# panelolu_2_1.net
KiCad netlist of a schematic drawn in EAGLE
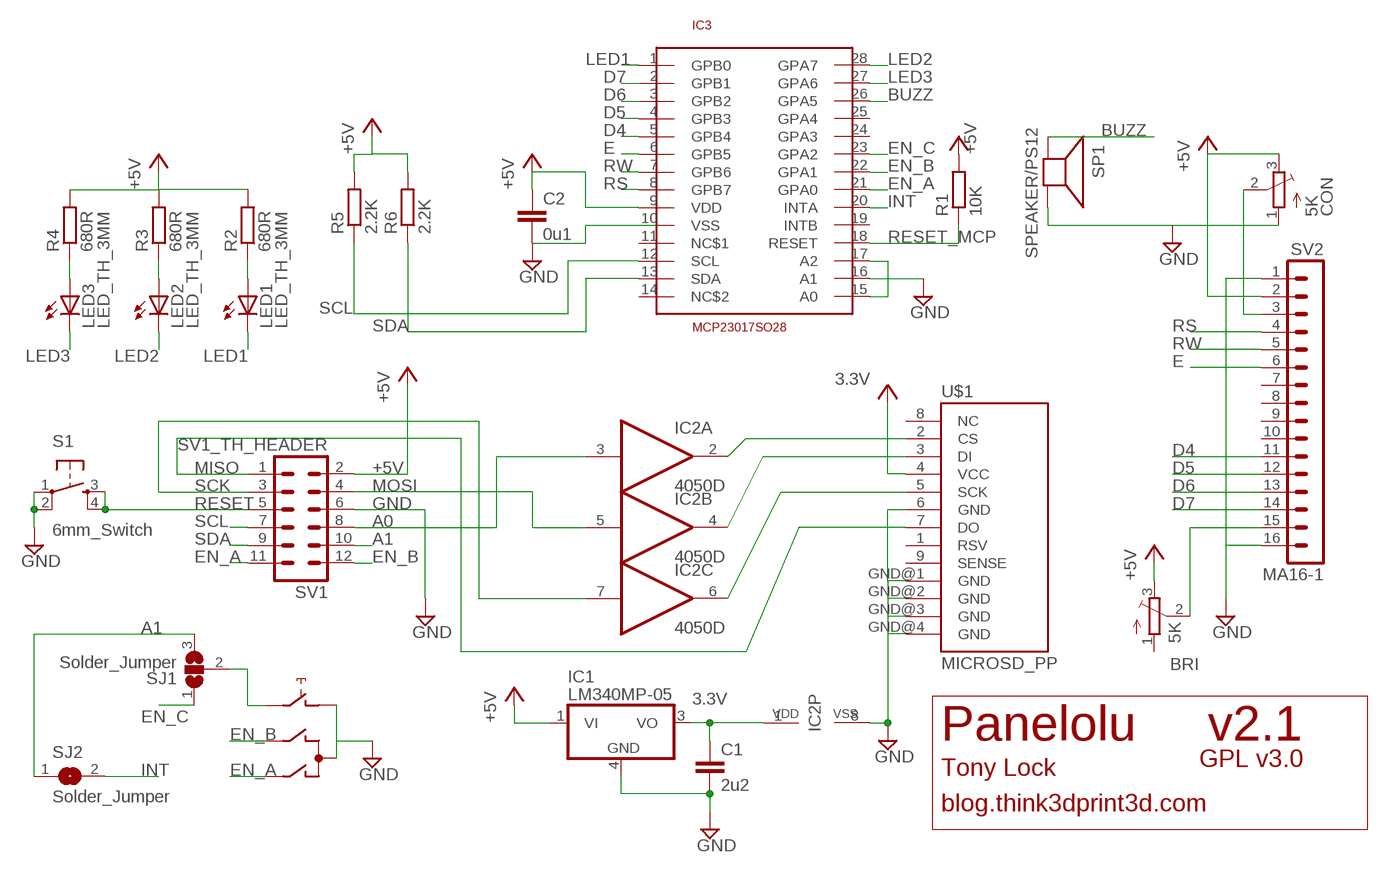
[diagram p0: schematic, sheet 1]

(export (version "E")
  (design (tool "Eeschema 10.0.6"))
  (components
    (comp (ref "BRI")
      (value "5K")
      (footprint "eagle-import:TC33X")
      (libsource (lib "eagle-import") (part "TRIMPOTTC33X"))
    )
    (comp (ref "C1")
      (value "2u2")
      (footprint "eagle-import:C1206K")
      (libsource (lib "eagle-import") (part "C-EUC1206K"))
    )
    (comp (ref "C2")
      (value "0u1")
      (footprint "eagle-import:C0805K")
      (libsource (lib "eagle-import") (part "resistor_C-EUC0805K"))
    )
    (comp (ref "CON")
      (value "5K")
      (footprint "eagle-import:TC33X")
      (libsource (lib "eagle-import") (part "TRIMPOTTC33X"))
    )
    (comp (ref "IC1")
      (value "LM340MP-05")
      (footprint "eagle-import:SOT223")
      (libsource (lib "eagle-import") (part "LM340?-MP05"))
    )
    (comp (ref "IC2")
      (value "4050D")
      (footprint "eagle-import:SO16")
      (libsource (lib "eagle-import") (part "4050D"))
    )
    (comp (ref "IC3")
      (value "MCP23017SO28")
      (footprint "eagle-import:SO28W")
      (libsource (lib "eagle-import") (part "MCP23017SO28"))
    )
    (comp (ref "LED1")
      (value "LED_TH_3MM")
      (footprint "eagle-import:LED3MM")
      (libsource (lib "eagle-import") (part "LED3MM"))
    )
    (comp (ref "LED2")
      (value "LED_TH_3MM")
      (footprint "eagle-import:LED3MM")
      (libsource (lib "eagle-import") (part "LED3MM"))
    )
    (comp (ref "LED3")
      (value "LED_TH_3MM")
      (footprint "eagle-import:LED3MM")
      (libsource (lib "eagle-import") (part "LED3MM"))
    )
    (comp (ref "R1")
      (value "10K")
      (footprint "eagle-import:M0805")
      (libsource (lib "eagle-import") (part "R-EU_M0805"))
    )
    (comp (ref "R2")
      (value "680R")
      (footprint "eagle-import:M0805")
      (libsource (lib "eagle-import") (part "R-EU_M0805"))
    )
    (comp (ref "R3")
      (value "680R")
      (footprint "eagle-import:M0805")
      (libsource (lib "eagle-import") (part "R-EU_M0805"))
    )
    (comp (ref "R4")
      (value "680R")
      (footprint "eagle-import:M0805")
      (libsource (lib "eagle-import") (part "R-EU_M0805"))
    )
    (comp (ref "R5")
      (value "2.2K")
      (footprint "eagle-import:M0805")
      (libsource (lib "eagle-import") (part "R-EU_M0805"))
    )
    (comp (ref "R6")
      (value "2.2K")
      (footprint "eagle-import:M0805")
      (libsource (lib "eagle-import") (part "R-EU_M0805"))
    )
    (comp (ref "S1")
      (value "6mm_Switch")
      (footprint "eagle-import:TACTILE-PTH")
      (libsource (lib "eagle-import") (part "TAC_SWITCHPTH"))
    )
    (comp (ref "SJ1")
      (value "Solder_Jumper")
      (footprint "eagle-import:SJ_2")
      (libsource (lib "eagle-import") (part "SJ2W"))
    )
    (comp (ref "SJ2")
      (value "Solder_Jumper")
      (footprint "eagle-import:SJ")
      (libsource (lib "eagle-import") (part "SJ"))
    )
    (comp (ref "SP1")
      (value "SPEAKER/PS12")
      (footprint "eagle-import:PS12")
      (libsource (lib "eagle-import") (part "SPEAKER/PS12"))
    )
    (comp (ref "SV1")
      (value "SV1_TH_HEADER")
      (footprint "eagle-import:MA06-2")
      (libsource (lib "eagle-import") (part "MA06-2"))
    )
    (comp (ref "SV2")
      (value "MA16-1")
      (footprint "eagle-import:MA16-1")
      (libsource (lib "eagle-import") (part "MA16-1"))
    )
    (comp (ref "SW1")
      (value "EC12E_SW")
      (footprint "eagle-import:ALPS_EC12E_SW")
      (fields (field (name "MPN") "EC12E2424407"))
      (libsource (lib "eagle-import") (part "EC12E_SW"))
    )
    (comp (ref "U$1")
      (value "MICROSD_PP")
      (footprint "eagle-import:MICROSD_PP")
      (libsource (lib "eagle-import") (part "MICROSD_PP"))
    )
  )
  (nets
    (net (code "1") (name "+5V") (class "Default")
      (node (ref "BRI") (pin "3") (pinfunction "E_3") (pintype "passive"))
      (node (ref "C2") (pin "1") (pinfunction "1_1") (pintype "passive"))
      (node (ref "CON") (pin "3") (pinfunction "E_3") (pintype "passive"))
      (node (ref "IC1") (pin "1") (pinfunction "VI_1") (pintype "input"))
      (node (ref "IC3") (pin "9") (pinfunction "VDD_9") (pintype "power_in"))
      (node (ref "R1") (pin "2") (pinfunction "2_2") (pintype "passive"))
      (node (ref "R2") (pin "2") (pinfunction "2_2") (pintype "passive"))
      (node (ref "R3") (pin "2") (pinfunction "2_2") (pintype "passive"))
      (node (ref "R4") (pin "2") (pinfunction "2_2") (pintype "passive"))
      (node (ref "R5") (pin "2") (pinfunction "2_2") (pintype "passive"))
      (node (ref "R6") (pin "2") (pinfunction "2_2") (pintype "passive"))
      (node (ref "SV1") (pin "2") (pinfunction "2_2") (pintype "passive"))
      (node (ref "SV2") (pin "2") (pinfunction "2_2") (pintype "passive"))
    )
    (net (code "2") (name "/A0") (class "Default")
      (node (ref "IC2") (pin "3") (pinfunction "I_3") (pintype "input"))
      (node (ref "SV1") (pin "8") (pinfunction "8_8") (pintype "passive"))
    )
    (net (code "3") (name "/A1") (class "Default")
      (node (ref "SJ1") (pin "3") (pinfunction "3_3") (pintype "passive"))
      (node (ref "SJ2") (pin "1") (pinfunction "1_1") (pintype "passive"))
      (node (ref "SV1") (pin "10") (pinfunction "10_10") (pintype "passive"))
    )
    (net (code "4") (name "/BUZZ") (class "Default")
      (node (ref "IC3") (pin "26") (pinfunction "GPA5_26") (pintype "bidirectional"))
      (node (ref "SP1") (pin "P$1") (pinfunction "+_P$1") (pintype "passive"))
    )
    (net (code "5") (name "/D4") (class "Default")
      (node (ref "IC3") (pin "5") (pinfunction "GPB4_5") (pintype "bidirectional"))
      (node (ref "SV2") (pin "11") (pinfunction "11_11") (pintype "passive"))
    )
    (net (code "6") (name "/D5") (class "Default")
      (node (ref "IC3") (pin "4") (pinfunction "GPB3_4") (pintype "bidirectional"))
      (node (ref "SV2") (pin "12") (pinfunction "12_12") (pintype "passive"))
    )
    (net (code "7") (name "/D6") (class "Default")
      (node (ref "IC3") (pin "3") (pinfunction "GPB2_3") (pintype "bidirectional"))
      (node (ref "SV2") (pin "13") (pinfunction "13_13") (pintype "passive"))
    )
    (net (code "8") (name "/D7") (class "Default")
      (node (ref "IC3") (pin "2") (pinfunction "GPB1_2") (pintype "bidirectional"))
      (node (ref "SV2") (pin "14") (pinfunction "14_14") (pintype "passive"))
    )
    (net (code "9") (name "/E") (class "Default")
      (node (ref "IC3") (pin "6") (pinfunction "GPB5_6") (pintype "bidirectional"))
      (node (ref "SV2") (pin "6") (pinfunction "6_6") (pintype "passive"))
    )
    (net (code "10") (name "/EN_A") (class "Default")
      (node (ref "IC3") (pin "21") (pinfunction "GPA0_21") (pintype "bidirectional"))
      (node (ref "SV1") (pin "11") (pinfunction "11_11") (pintype "passive"))
      (node (ref "SW1") (pin "A") (pinfunction "A_A") (pintype "passive"))
    )
    (net (code "11") (name "/EN_B") (class "Default")
      (node (ref "IC3") (pin "22") (pinfunction "GPA1_22") (pintype "bidirectional"))
      (node (ref "SV1") (pin "12") (pinfunction "12_12") (pintype "passive"))
      (node (ref "SW1") (pin "B") (pinfunction "B_B") (pintype "passive"))
    )
    (net (code "12") (name "/EN_C") (class "Default")
      (node (ref "IC3") (pin "23") (pinfunction "GPA2_23") (pintype "bidirectional"))
      (node (ref "SJ1") (pin "1") (pinfunction "1_1") (pintype "passive"))
    )
    (net (code "13") (name "/INT") (class "Default")
      (node (ref "IC3") (pin "20") (pinfunction "INTA_20") (pintype "output"))
      (node (ref "SJ2") (pin "2") (pinfunction "2_2") (pintype "passive"))
    )
    (net (code "14") (name "/LED1") (class "Default")
      (node (ref "IC3") (pin "1") (pinfunction "GPB0_1") (pintype "bidirectional"))
      (node (ref "LED1") (pin "K") (pinfunction "C_K") (pintype "passive"))
    )
    (net (code "15") (name "/LED2") (class "Default")
      (node (ref "IC3") (pin "28") (pinfunction "GPA7_28") (pintype "bidirectional"))
      (node (ref "LED2") (pin "K") (pinfunction "C_K") (pintype "passive"))
    )
    (net (code "16") (name "/LED3") (class "Default")
      (node (ref "IC3") (pin "27") (pinfunction "GPA6_27") (pintype "bidirectional"))
      (node (ref "LED3") (pin "K") (pinfunction "C_K") (pintype "passive"))
    )
    (net (code "17") (name "/MISO") (class "Default")
      (node (ref "SV1") (pin "1") (pinfunction "1_1") (pintype "passive"))
      (node (ref "U$1") (pin "7") (pinfunction "DO_7") (pintype "bidirectional"))
    )
    (net (code "18") (name "/MOSI") (class "Default")
      (node (ref "IC2") (pin "5") (pinfunction "I_5") (pintype "input"))
      (node (ref "SV1") (pin "4") (pinfunction "4_4") (pintype "passive"))
    )
    (net (code "19") (name "/RESET") (class "Default")
      (node (ref "S1") (pin "3") (pinfunction "3_3") (pintype "passive"))
      (node (ref "S1") (pin "4") (pinfunction "4_4") (pintype "passive"))
      (node (ref "SV1") (pin "5") (pinfunction "5_5") (pintype "passive"))
    )
    (net (code "20") (name "/RESET_MCP") (class "Default")
      (node (ref "IC3") (pin "18") (pinfunction "RESET_18") (pintype "output"))
      (node (ref "R1") (pin "1") (pinfunction "1_1") (pintype "passive"))
    )
    (net (code "21") (name "/RS") (class "Default")
      (node (ref "IC3") (pin "8") (pinfunction "GPB7_8") (pintype "bidirectional"))
      (node (ref "SV2") (pin "4") (pinfunction "4_4") (pintype "passive"))
    )
    (net (code "22") (name "/RW") (class "Default")
      (node (ref "IC3") (pin "7") (pinfunction "GPB6_7") (pintype "bidirectional"))
      (node (ref "SV2") (pin "5") (pinfunction "5_5") (pintype "passive"))
    )
    (net (code "23") (name "/SCK") (class "Default")
      (node (ref "IC2") (pin "7") (pinfunction "I_7") (pintype "input"))
      (node (ref "SV1") (pin "3") (pinfunction "3_3") (pintype "passive"))
    )
    (net (code "24") (name "/SCL") (class "Default")
      (node (ref "IC3") (pin "12") (pinfunction "SCL_12") (pintype "input"))
      (node (ref "R5") (pin "1") (pinfunction "1_1") (pintype "passive"))
      (node (ref "SV1") (pin "7") (pinfunction "7_7") (pintype "passive"))
    )
    (net (code "25") (name "/SDA") (class "Default")
      (node (ref "IC3") (pin "13") (pinfunction "SDA_13") (pintype "bidirectional"))
      (node (ref "R6") (pin "1") (pinfunction "1_1") (pintype "passive"))
      (node (ref "SV1") (pin "9") (pinfunction "9_9") (pintype "passive"))
    )
    (net (code "26") (name "3.3V") (class "Default")
      (node (ref "C1") (pin "1") (pinfunction "1_1") (pintype "passive"))
      (node (ref "IC1") (pin "3") (pinfunction "VO_3") (pintype "passive"))
      (node (ref "IC2") (pin "1") (pinfunction "VDD_1") (pintype "power_in"))
      (node (ref "U$1") (pin "4") (pinfunction "VCC_4") (pintype "bidirectional"))
    )
    (net (code "27") (name "GND") (class "Default")
      (node (ref "C1") (pin "2") (pinfunction "2_2") (pintype "passive"))
      (node (ref "C2") (pin "2") (pinfunction "2_2") (pintype "passive"))
      (node (ref "CON") (pin "1") (pinfunction "A_1") (pintype "passive"))
      (node (ref "IC1") (pin "4") (pinfunction "GND_4") (pintype "passive"))
      (node (ref "IC2") (pin "8") (pinfunction "VSS_8") (pintype "power_in"))
      (node (ref "IC3") (pin "10") (pinfunction "VSS_10") (pintype "power_in"))
      (node (ref "IC3") (pin "15") (pinfunction "A0_15") (pintype "input"))
      (node (ref "IC3") (pin "16") (pinfunction "A1_16") (pintype "input"))
      (node (ref "IC3") (pin "17") (pinfunction "A2_17") (pintype "input"))
      (node (ref "S1") (pin "1") (pinfunction "1_1") (pintype "passive"))
      (node (ref "S1") (pin "2") (pinfunction "2_2") (pintype "passive"))
      (node (ref "SP1") (pin "P$2") (pinfunction "-_P$2") (pintype "passive"))
      (node (ref "SV1") (pin "6") (pinfunction "6_6") (pintype "passive"))
      (node (ref "SV2") (pin "1") (pinfunction "1_1") (pintype "passive"))
      (node (ref "SV2") (pin "16") (pinfunction "16_16") (pintype "passive"))
      (node (ref "SW1") (pin "C") (pinfunction "C_C") (pintype "passive"))
      (node (ref "SW1") (pin "D") (pinfunction "1_D") (pintype "passive"))
      (node (ref "U$1") (pin "6") (pinfunction "GND_6") (pintype "bidirectional"))
      (node (ref "U$1") (pin "GND@1") (pinfunction "GND_GND@1") (pintype "bidirectional"))
      (node (ref "U$1") (pin "GND@2") (pinfunction "GND_GND@2") (pintype "bidirectional"))
      (node (ref "U$1") (pin "GND@3") (pinfunction "GND_GND@3") (pintype "bidirectional"))
      (node (ref "U$1") (pin "GND@4") (pinfunction "GND_GND@4") (pintype "bidirectional"))
    )
    (net (code "28") (name "Net-(BRI-S)") (class "Default")
      (node (ref "BRI") (pin "2") (pinfunction "S_2") (pintype "passive"))
      (node (ref "SV2") (pin "15") (pinfunction "15_15") (pintype "passive"))
    )
    (net (code "29") (name "Net-(CON-S)") (class "Default")
      (node (ref "CON") (pin "2") (pinfunction "S_2") (pintype "passive"))
      (node (ref "SV2") (pin "3") (pinfunction "3_3") (pintype "passive"))
    )
    (net (code "30") (name "Net-(IC2A-O)") (class "Default")
      (node (ref "IC2") (pin "2") (pinfunction "O_2") (pintype "output"))
      (node (ref "U$1") (pin "2") (pinfunction "CS_2") (pintype "bidirectional"))
    )
    (net (code "31") (name "Net-(IC2B-O)") (class "Default")
      (node (ref "IC2") (pin "4") (pinfunction "O_4") (pintype "output"))
      (node (ref "U$1") (pin "3") (pinfunction "DI_3") (pintype "bidirectional"))
    )
    (net (code "32") (name "Net-(IC2C-O)") (class "Default")
      (node (ref "IC2") (pin "6") (pinfunction "O_6") (pintype "output"))
      (node (ref "U$1") (pin "5") (pinfunction "SCK_5") (pintype "bidirectional"))
    )
    (net (code "33") (name "Net-(LED1-PadA)") (class "Default")
      (node (ref "LED1") (pin "A") (pinfunction "A_A") (pintype "passive"))
      (node (ref "R2") (pin "1") (pinfunction "1_1") (pintype "passive"))
    )
    (net (code "34") (name "Net-(LED2-PadA)") (class "Default")
      (node (ref "LED2") (pin "A") (pinfunction "A_A") (pintype "passive"))
      (node (ref "R3") (pin "1") (pinfunction "1_1") (pintype "passive"))
    )
    (net (code "35") (name "Net-(LED3-PadA)") (class "Default")
      (node (ref "LED3") (pin "A") (pinfunction "A_A") (pintype "passive"))
      (node (ref "R4") (pin "1") (pinfunction "1_1") (pintype "passive"))
    )
    (net (code "36") (name "Net-(SW1B-2)") (class "Default")
      (node (ref "SJ1") (pin "2") (pinfunction "2_2") (pintype "passive"))
      (node (ref "SW1") (pin "E") (pinfunction "2_E") (pintype "passive"))
    )
    (net (code "37") (name "unconnected-(BRI-A-Pad1)") (class "Default")
      (node (ref "BRI") (pin "1") (pinfunction "A_1") (pintype "passive"))
    )
    (net (code "38") (name "unconnected-(IC3-GPA3-Pad24)") (class "Default")
      (node (ref "IC3") (pin "24") (pinfunction "GPA3_24") (pintype "bidirectional"))
    )
    (net (code "39") (name "unconnected-(IC3-GPA4-Pad25)") (class "Default")
      (node (ref "IC3") (pin "25") (pinfunction "GPA4_25") (pintype "bidirectional"))
    )
    (net (code "40") (name "unconnected-(IC3-INTB-Pad19)") (class "Default")
      (node (ref "IC3") (pin "19") (pinfunction "INTB_19") (pintype "output"))
    )
    (net (code "41") (name "unconnected-(IC3-NC$1-Pad11)") (class "Default")
      (node (ref "IC3") (pin "11") (pinfunction "NC$1_11") (pintype "no_connect"))
    )
    (net (code "42") (name "unconnected-(IC3-NC$2-Pad14)") (class "Default")
      (node (ref "IC3") (pin "14") (pinfunction "NC$2_14") (pintype "no_connect"))
    )
    (net (code "43") (name "unconnected-(SV2-Pad7)") (class "Default")
      (node (ref "SV2") (pin "7") (pinfunction "7_7") (pintype "passive"))
    )
    (net (code "44") (name "unconnected-(SV2-Pad8)") (class "Default")
      (node (ref "SV2") (pin "8") (pinfunction "8_8") (pintype "passive"))
    )
    (net (code "45") (name "unconnected-(SV2-Pad9)") (class "Default")
      (node (ref "SV2") (pin "9") (pinfunction "9_9") (pintype "passive"))
    )
    (net (code "46") (name "unconnected-(SV2-Pad10)") (class "Default")
      (node (ref "SV2") (pin "10") (pinfunction "10_10") (pintype "passive"))
    )
    (net (code "47") (name "unconnected-(U$1-NC-Pad8)") (class "Default")
      (node (ref "U$1") (pin "8") (pinfunction "NC_8") (pintype "bidirectional"))
    )
    (net (code "48") (name "unconnected-(U$1-RSV-Pad1)") (class "Default")
      (node (ref "U$1") (pin "1") (pinfunction "RSV_1") (pintype "bidirectional"))
    )
    (net (code "49") (name "unconnected-(U$1-SENSE-Pad9)") (class "Default")
      (node (ref "U$1") (pin "9") (pinfunction "SENSE_9") (pintype "bidirectional"))
    )
  )
)
